# Temperature.net
KiCad netlist of a schematic drawn in Altium Designer
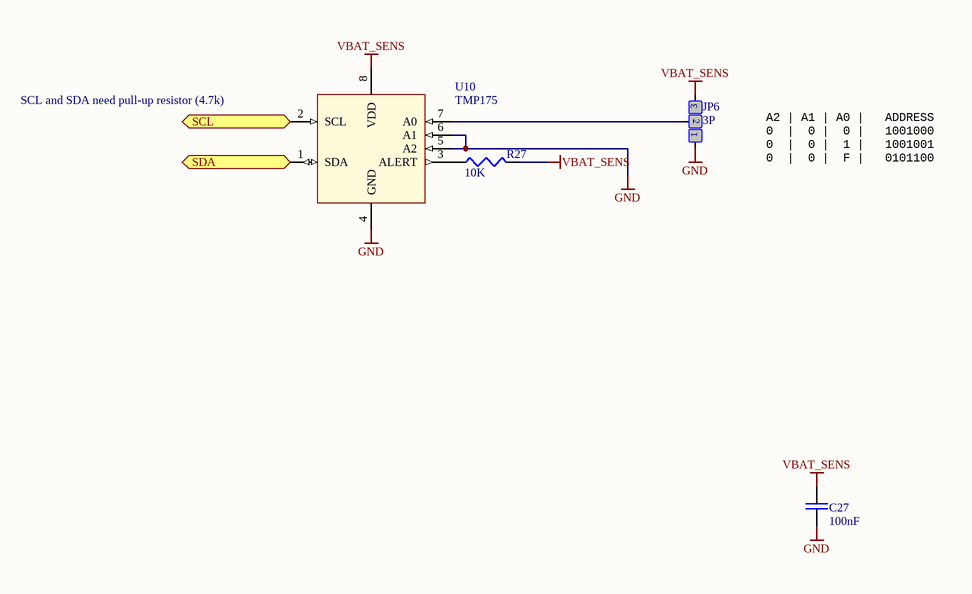
[diagram p0: Temperature.SchDoc]

(export (version "E")
  (design (tool "Eeschema 10.0.6"))
  (components
    (comp (ref "C27")
      (value "100nF")
      (footprint "0603")
      (description "Capacitor")
      (fields (field (name "OWNER") "Nuno Brum"))
      (libsource (lib "Alcetronics_Devices") (part "CAP"))
    )
    (comp (ref "JP6")
      (value "3P")
      (footprint "SOLDER-3-0603")
      (description "Solder Jumper 3 positions")
      (fields (field (name "OWNER") "Rui Rebelo"))
      (libsource (lib "Alcetronics_EM") (part "SOLDER3"))
    )
    (comp (ref "R27")
      (value "10K")
      (footprint "0603")
      (description "Resistor")
      (fields (field (name "OWNER") "Nuno Brum"))
      (libsource (lib "Alcetronics_Devices") (part "RES"))
    )
    (comp (ref "U10")
      (value "TMP175")
      (footprint "SOIC-8")
      (description "Digital Temperature Sensor")
      (libsource (lib "Alcetronics_IC") (part "TMP175"))
    )
  )
  (nets
    (net (code "1") (name "/SCL") (class "Default")
      (node (ref "U10") (pin "2") (pinfunction "SCL_2") (pintype "input"))
    )
    (net (code "2") (name "/SDA") (class "Default")
      (node (ref "U10") (pin "1") (pinfunction "SDA_1") (pintype "bidirectional"))
    )
    (net (code "3") (name "GND") (class "Default")
      (node (ref "C27") (pin "1") (pinfunction "1_1") (pintype "passive"))
      (node (ref "JP6") (pin "1") (pinfunction "1_1") (pintype "passive"))
      (node (ref "U10") (pin "4") (pinfunction "GND_4") (pintype "power_in"))
      (node (ref "U10") (pin "5") (pinfunction "A2_5") (pintype "input"))
      (node (ref "U10") (pin "6") (pinfunction "A1_6") (pintype "input"))
    )
    (net (code "4") (name "Net-(U10-A0)") (class "Default")
      (node (ref "JP6") (pin "2") (pinfunction "2_2") (pintype "passive"))
      (node (ref "U10") (pin "7") (pinfunction "A0_7") (pintype "input"))
    )
    (net (code "5") (name "Net-(U10-ALERT)") (class "Default")
      (node (ref "R27") (pin "1") (pinfunction "1_1") (pintype "passive"))
      (node (ref "U10") (pin "3") (pinfunction "ALERT_3") (pintype "output"))
    )
    (net (code "6") (name "VBAT_SENS") (class "Default")
      (node (ref "C27") (pin "2") (pinfunction "2_2") (pintype "passive"))
      (node (ref "JP6") (pin "3") (pinfunction "3_3") (pintype "passive"))
      (node (ref "R27") (pin "2") (pinfunction "2_2") (pintype "passive"))
      (node (ref "U10") (pin "8") (pinfunction "VDD_8") (pintype "power_in"))
    )
  )
)
